# Connectors.net
KiCad netlist of a schematic drawn in Altium Designer
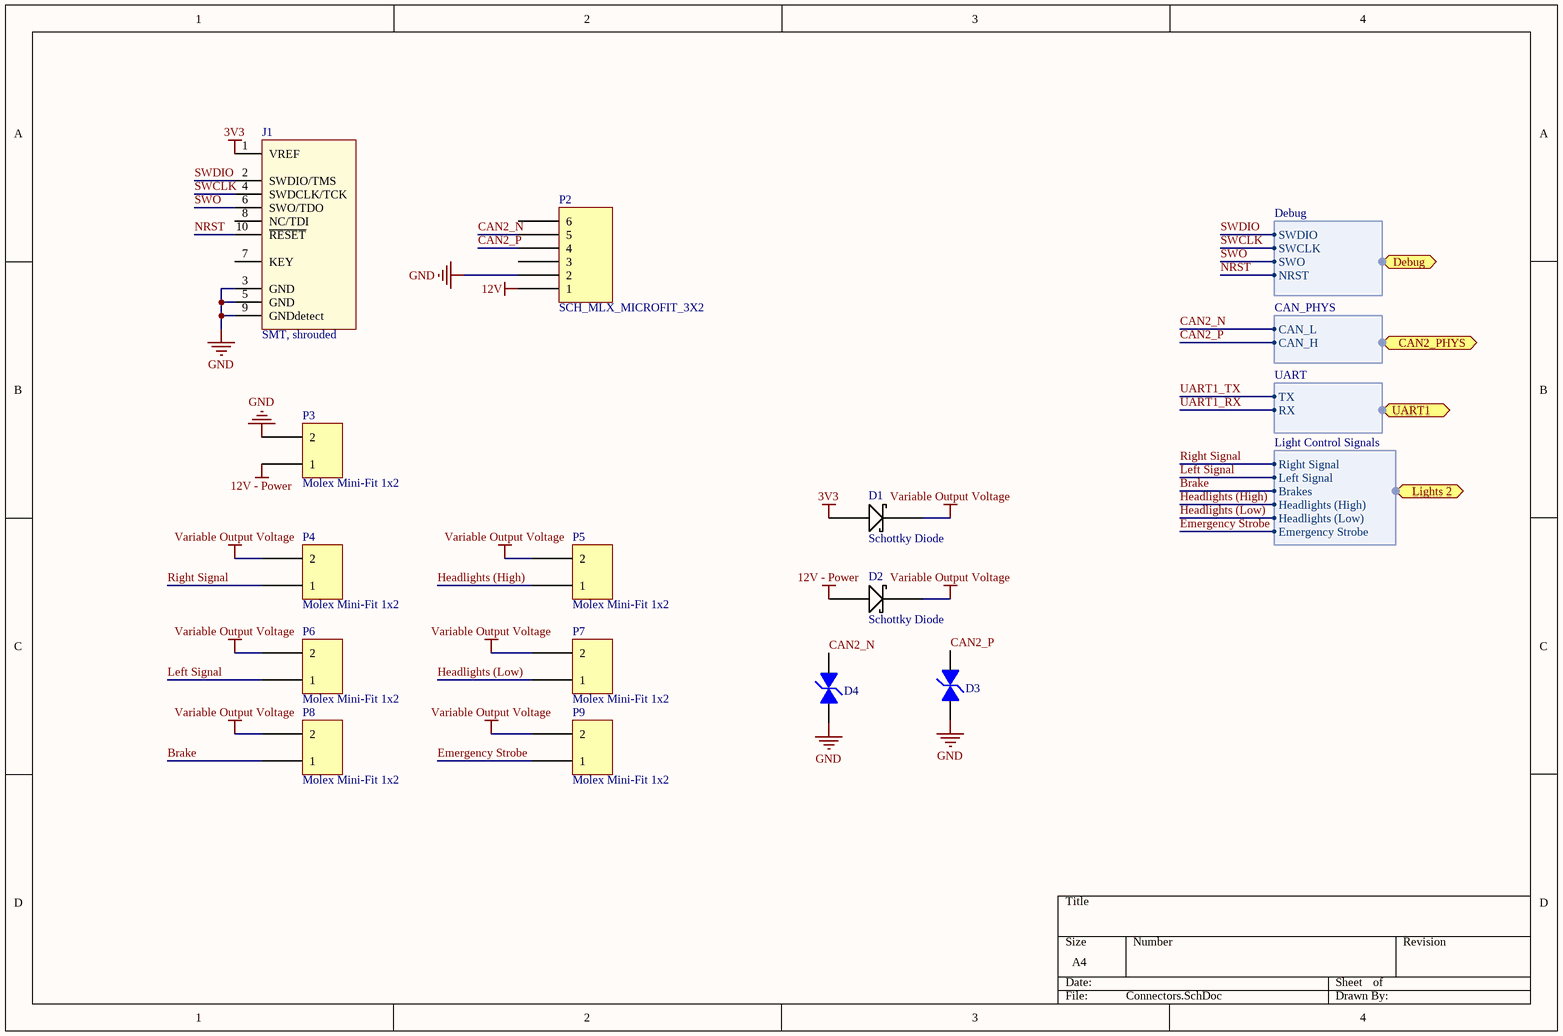
[diagram p0: Connectors.SchDoc]

(export (version "E")
  (design (tool "Eeschema 10.0.6"))
  (components
    (comp (ref "D1")
      (value "Schottky Diode")
      (footprint "ON Semi Schottky Diode - MBRM110LT1G")
      (libsource (lib "ON Semi Schottky Diode") (part "ON Semi Schottky Diode - MBRM110LT1G"))
    )
    (comp (ref "D2")
      (value "Schottky Diode")
      (footprint "ON Semi Schottky Diode - MBRM110LT1G")
      (libsource (lib "ON Semi Schottky Diode") (part "ON Semi Schottky Diode - MBRM110LT1G"))
    )
    (comp (ref "D3")
      (value "TVS Diode")
      (footprint "TVS Diode")
      (fields (field (name "MANUFACTURER") "Bourns"))
      (libsource (lib "TVS Diode") (part "TVS Diode"))
    )
    (comp (ref "D4")
      (value "TVS Diode")
      (footprint "TVS Diode")
      (fields (field (name "MANUFACTURER") "Bourns"))
      (libsource (lib "TVS Diode") (part "TVS Diode"))
    )
    (comp (ref "J1")
      (value "SMT, shrouded")
      (footprint "CONN-50mil-10POS-SMD")
      (description "ARM Cortex-M 10pin connector,shrouded,SMT")
      (libsource (lib "CONN-50mil-cortexM") (part "conn_0.050{dblquote}_cortexM"))
    )
    (comp (ref "P2")
      (value "SCH_MLX_MICROFIT_3X2")
      (footprint "PCB_MLX_MICROFIT_3X2")
      (libsource (lib "Molex Microfit 3.0 3x2") (part "SCH_MLX_MICROFIT_3X2"))
    )
    (comp (ref "P3")
      (value "Molex Mini-Fit 1x2")
      (footprint "Molex Mini-Fit Jr 2x1")
      (libsource (lib "Molex Mini-Fit Jr 1x2") (part "Molex Mini-Fit 1x2"))
    )
    (comp (ref "P4")
      (value "Molex Mini-Fit 1x2")
      (footprint "Molex Mini-Fit Jr 2x1")
      (libsource (lib "Molex Mini-Fit Jr 1x2") (part "Molex Mini-Fit 1x2"))
    )
    (comp (ref "P5")
      (value "Molex Mini-Fit 1x2")
      (footprint "Molex Mini-Fit Jr 2x1")
      (libsource (lib "Molex Mini-Fit Jr 1x2") (part "Molex Mini-Fit 1x2"))
    )
    (comp (ref "P6")
      (value "Molex Mini-Fit 1x2")
      (footprint "Molex Mini-Fit Jr 2x1")
      (libsource (lib "Molex Mini-Fit Jr 1x2") (part "Molex Mini-Fit 1x2"))
    )
    (comp (ref "P7")
      (value "Molex Mini-Fit 1x2")
      (footprint "Molex Mini-Fit Jr 2x1")
      (libsource (lib "Molex Mini-Fit Jr 1x2") (part "Molex Mini-Fit 1x2"))
    )
    (comp (ref "P8")
      (value "Molex Mini-Fit 1x2")
      (footprint "Molex Mini-Fit Jr 2x1")
      (libsource (lib "Molex Mini-Fit Jr 1x2") (part "Molex Mini-Fit 1x2"))
    )
    (comp (ref "P9")
      (value "Molex Mini-Fit 1x2")
      (footprint "Molex Mini-Fit Jr 2x1")
      (libsource (lib "Molex Mini-Fit Jr 1x2") (part "Molex Mini-Fit 1x2"))
    )
  )
  (nets
    (net (code "7") (name "/Brake") (class "Default")
      (node (ref "P8") (pin "1") (pinfunction "1_1") (pintype "passive"))
    )
    (net (code "8") (name "/CAN2_N") (class "Default")
      (node (ref "D4") (pin "1") (pintype "passive"))
      (node (ref "P2") (pin "5") (pinfunction "5_5") (pintype "passive"))
    )
    (net (code "9") (name "/CAN2_P") (class "Default")
      (node (ref "D3") (pin "1") (pintype "passive"))
      (node (ref "P2") (pin "4") (pinfunction "4_4") (pintype "passive"))
    )
    (net (code "10") (name "/Emergency Strobe") (class "Default")
      (node (ref "P9") (pin "1") (pinfunction "1_1") (pintype "passive"))
    )
    (net (code "11") (name "/Headlights (High)") (class "Default")
      (node (ref "P5") (pin "1") (pinfunction "1_1") (pintype "passive"))
    )
    (net (code "12") (name "/Headlights (Low)") (class "Default")
      (node (ref "P7") (pin "1") (pinfunction "1_1") (pintype "passive"))
    )
    (net (code "13") (name "/Left Signal") (class "Default")
      (node (ref "P6") (pin "1") (pinfunction "1_1") (pintype "passive"))
    )
    (net (code "14") (name "/NRST") (class "Default")
      (node (ref "J1") (pin "10") (pinfunction "~{RESET}_10") (pintype "passive"))
    )
    (net (code "15") (name "/Right Signal") (class "Default")
      (node (ref "P4") (pin "1") (pinfunction "1_1") (pintype "passive"))
    )
    (net (code "16") (name "/SWCLK") (class "Default")
      (node (ref "J1") (pin "4") (pinfunction "SWDCLK/TCK_4") (pintype "passive"))
    )
    (net (code "17") (name "/SWDIO") (class "Default")
      (node (ref "J1") (pin "2") (pinfunction "SWDIO/TMS_2") (pintype "passive"))
    )
    (net (code "18") (name "/SWO") (class "Default")
      (node (ref "J1") (pin "6") (pinfunction "SWO/TDO_6") (pintype "passive"))
    )
    (net (code "25") (name "3V3") (class "Default")
      (node (ref "D1") (pin "2") (pinfunction "2_2") (pintype "passive"))
      (node (ref "J1") (pin "1") (pinfunction "VREF_1") (pintype "passive"))
    )
    (net (code "26") (name "12V") (class "Default")
      (node (ref "P2") (pin "1") (pinfunction "1_1") (pintype "passive"))
    )
    (net (code "27") (name "12V - Power") (class "Default")
      (node (ref "D2") (pin "2") (pinfunction "2_2") (pintype "passive"))
      (node (ref "P3") (pin "1") (pinfunction "1_1") (pintype "passive"))
    )
    (net (code "28") (name "GND") (class "Default")
      (node (ref "D3") (pin "2") (pintype "passive"))
      (node (ref "D4") (pin "2") (pintype "passive"))
      (node (ref "J1") (pin "3") (pinfunction "GND_3") (pintype "passive"))
      (node (ref "J1") (pin "5") (pinfunction "GND_5") (pintype "passive"))
      (node (ref "J1") (pin "9") (pinfunction "GNDdetect_9") (pintype "passive"))
      (node (ref "P2") (pin "2") (pinfunction "2_2") (pintype "passive"))
      (node (ref "P3") (pin "2") (pinfunction "2_2") (pintype "passive"))
    )
    (net (code "29") (name "Variable Output Voltage") (class "Default")
      (node (ref "D1") (pin "1") (pinfunction "1_1") (pintype "passive"))
      (node (ref "D2") (pin "1") (pinfunction "1_1") (pintype "passive"))
      (node (ref "P4") (pin "2") (pinfunction "2_2") (pintype "passive"))
      (node (ref "P5") (pin "2") (pinfunction "2_2") (pintype "passive"))
      (node (ref "P6") (pin "2") (pinfunction "2_2") (pintype "passive"))
      (node (ref "P7") (pin "2") (pinfunction "2_2") (pintype "passive"))
      (node (ref "P8") (pin "2") (pinfunction "2_2") (pintype "passive"))
      (node (ref "P9") (pin "2") (pinfunction "2_2") (pintype "passive"))
    )
    (net (code "30") (name "unconnected-(J1-KEY-Pad7)") (class "Default")
      (node (ref "J1") (pin "7") (pinfunction "KEY_7") (pintype "passive"))
    )
    (net (code "31") (name "unconnected-(J1-NC{slash}TDI-Pad8)") (class "Default")
      (node (ref "J1") (pin "8") (pinfunction "NC/TDI_8") (pintype "passive"))
    )
    (net (code "32") (name "unconnected-(P2-Pad3)") (class "Default")
      (node (ref "P2") (pin "3") (pinfunction "3_3") (pintype "passive"))
    )
    (net (code "33") (name "unconnected-(P2-Pad6)") (class "Default")
      (node (ref "P2") (pin "6") (pinfunction "6_6") (pintype "passive"))
    )
  )
)
